# 02_Power.net
KiCad netlist of a schematic drawn in Altium Designer
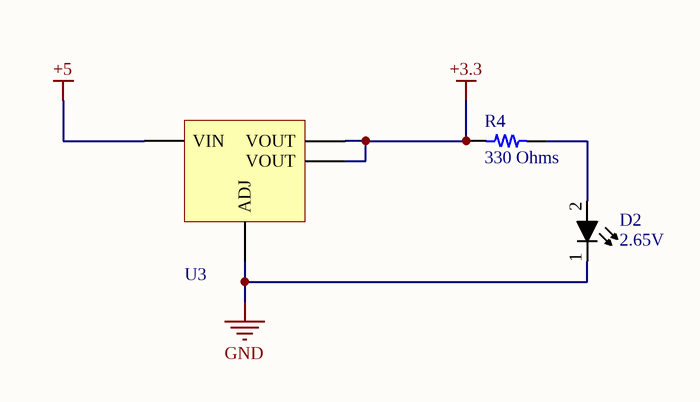
[diagram p0: 02_Power.SchDoc]

(export (version "E")
  (design (tool "Eeschema 10.0.6"))
  (components
    (comp (ref "D2")
      (value "diode_4")
      (footprint "chip_0603_LED")
      (description "LED, Green, 0603, Low current, HELI2 Series")
      (fields
        (field (name "FORWARD VOLTAGE") "2.65V")
        (field (name "PART NUMBER") "DIO-00050")
        (field (name "MANUFACTURER") "Kingbright")
      )
      (libsource (lib "Diodes") (part "diode_4"))
    )
    (comp (ref "R4")
      (value "330 Ohms")
      (footprint "RES 0603_1608")
      (description "RES 330 OHM 5% 1/8W 0603")
      (fields
        (field (name "PART NUMBER") "RK73B1JTTD331J")
        (field (name "MANUFACTURER") "KOA Speer Electronics, Inc.")
      )
      (libsource (lib "Celestial Altium Library - altium_library") (part "Resistor"))
    )
    (comp (ref "U3")
      (value "LM1117")
      (footprint "sot-223-4")
      (description "REG, Linear, Fixed 3V3, 800mA, SOT-223")
      (fields (field (name "PART NUMBER") "PWREG-00018") (field (name "MANUFACTURER") "TI"))
      (libsource (lib "cwrubotix_library") (part "LM1117"))
    )
  )
  (nets
    (net (code "1") (name "+3.3") (class "Default")
      (node (ref "R4") (pin "1") (pinfunction "1_1") (pintype "passive"))
      (node (ref "U3") (pin "2") (pinfunction "VOUT_2") (pintype "passive"))
      (node (ref "U3") (pin "4") (pinfunction "VOUT_4") (pintype "passive"))
    )
    (net (code "2") (name "+5") (class "Default")
      (node (ref "U3") (pin "3") (pinfunction "VIN_3") (pintype "passive"))
    )
    (net (code "3") (name "GND") (class "Default")
      (node (ref "D2") (pin "1") (pinfunction "1_1") (pintype "passive"))
      (node (ref "U3") (pin "1") (pinfunction "ADJ_1") (pintype "passive"))
    )
    (net (code "4") (name "Net-(D2-Pad2)") (class "Default")
      (node (ref "D2") (pin "2") (pinfunction "2_2") (pintype "passive"))
      (node (ref "R4") (pin "2") (pinfunction "2_2") (pintype "passive"))
    )
  )
)
